# HE6-RORO2.net
KiCad netlist of a schematic drawn in EAGLE
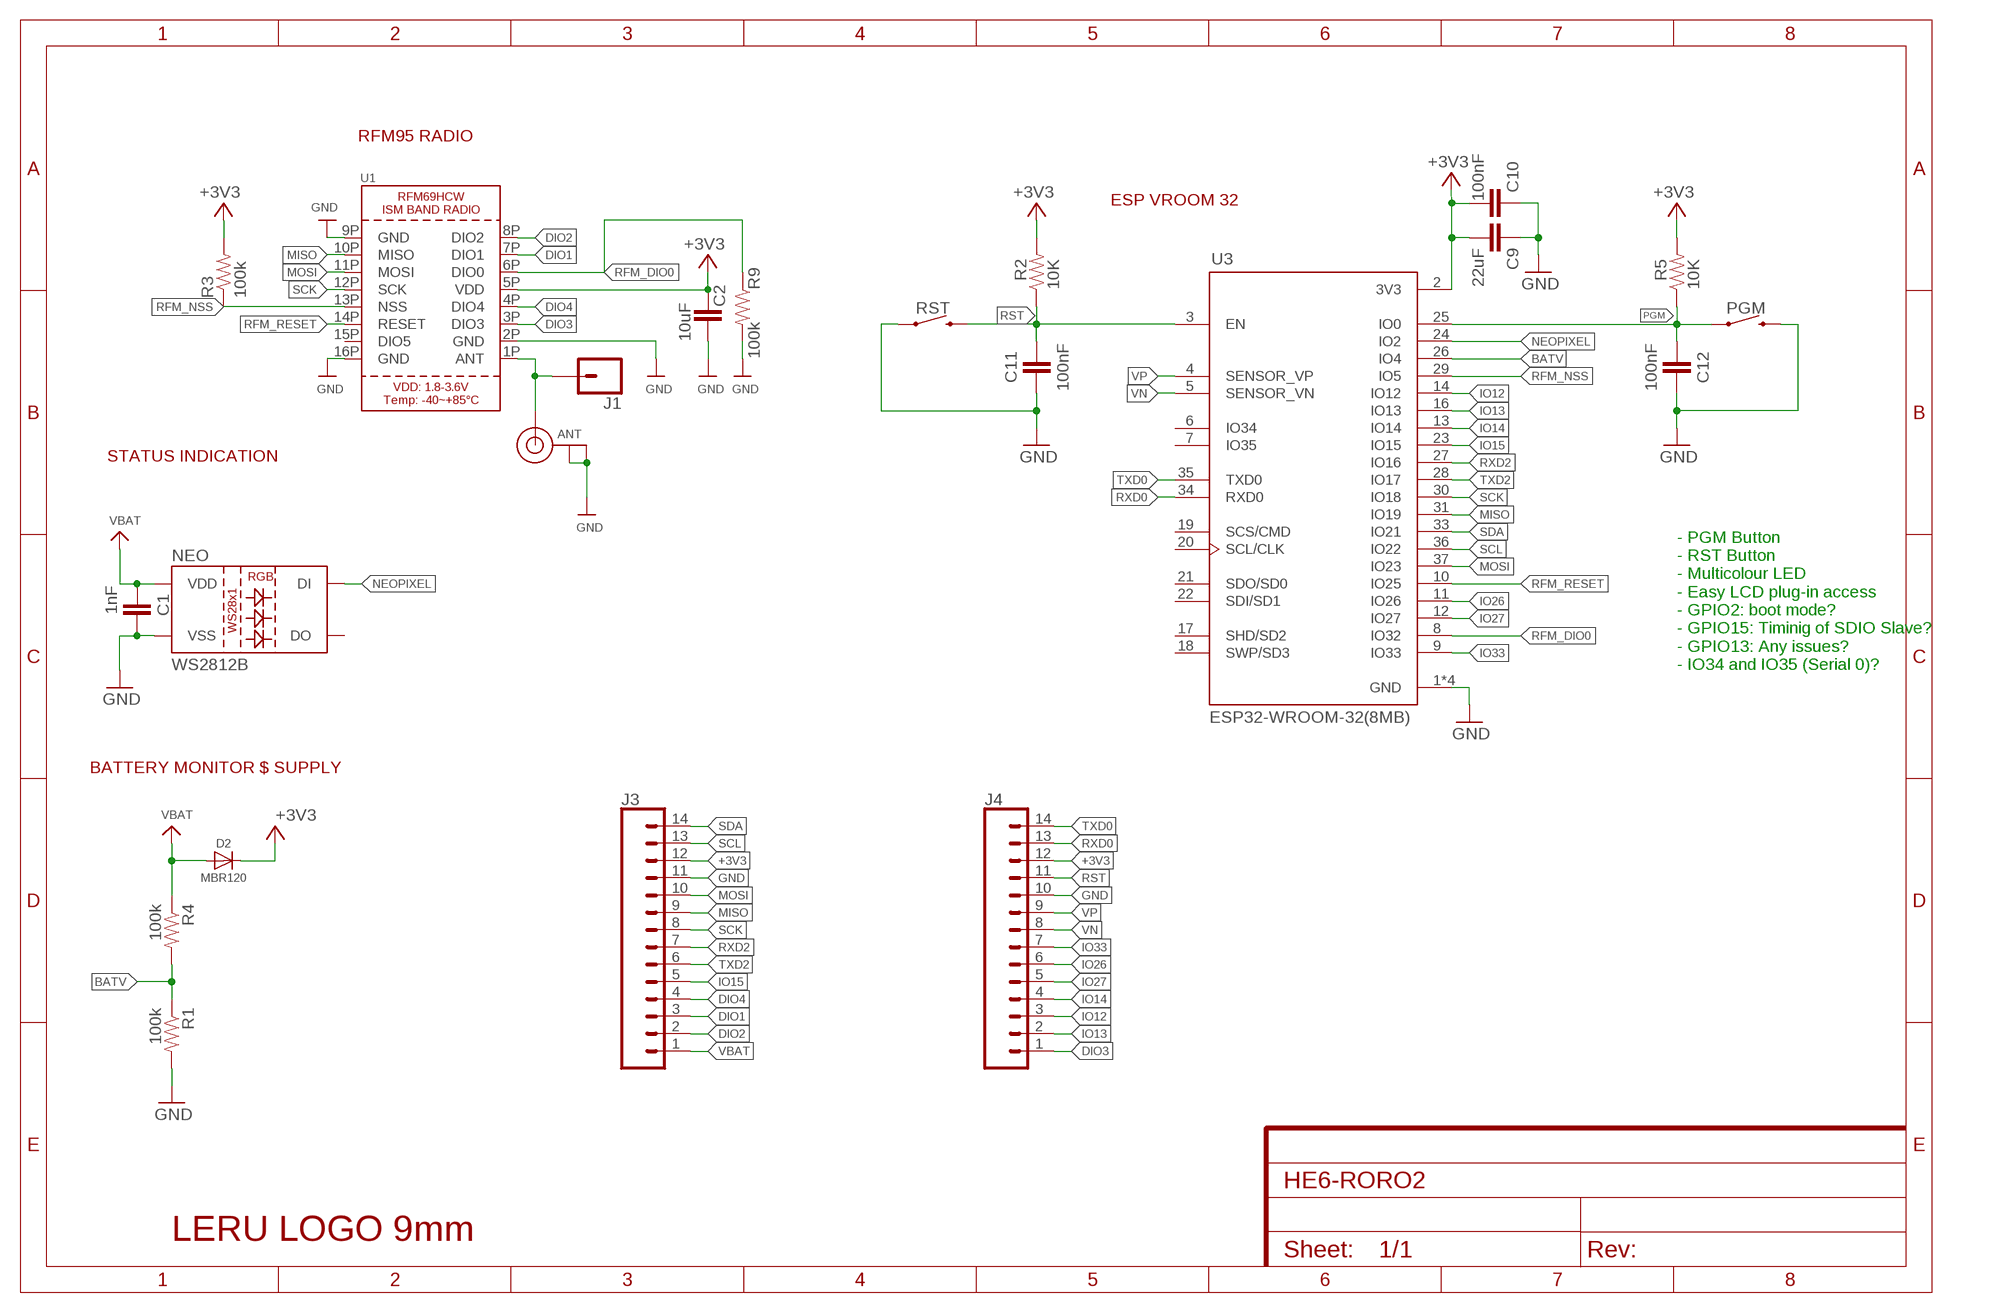
[diagram p0: schematic, sheet 1]

(export (version "E")
  (design (tool "Eeschema 10.0.6"))
  (components
    (comp (ref "ANT")
      (value "MICROBUILDER_ANTENNA_U.FL")
      (footprint "eagle-import:MICROBUILDER_U.FL")
      (libsource (lib "eagle-import") (part "MICROBUILDER_ANTENNA_U.FL"))
    )
    (comp (ref "C1")
      (value "1nF")
      (footprint "eagle-import:CAP")
      (libsource (lib "eagle-import") (part "CAP0805"))
    )
    (comp (ref "C2")
      (value "10uF")
      (footprint "eagle-import:CAP")
      (libsource (lib "eagle-import") (part "CAP0805"))
    )
    (comp (ref "C9")
      (value "22uF")
      (footprint "eagle-import:CAP")
      (libsource (lib "eagle-import") (part "CAP0805"))
    )
    (comp (ref "C10")
      (value "100nF")
      (footprint "eagle-import:CAP")
      (libsource (lib "eagle-import") (part "CAP0805"))
    )
    (comp (ref "C11")
      (value "100nF")
      (footprint "eagle-import:CAP")
      (libsource (lib "eagle-import") (part "CAP0805"))
    )
    (comp (ref "C12")
      (value "100nF")
      (footprint "eagle-import:CAP")
      (libsource (lib "eagle-import") (part "CAP0805"))
    )
    (comp (ref "D2")
      (value "MBR120")
      (footprint "eagle-import:DIODE")
      (libsource (lib "eagle-import") (part "DIODESOD123"))
    )
    (comp (ref "J1")
      (value "CONN_01PTH_NO_SILK_YES_STOP")
      (footprint "eagle-import:1X01_NO_SILK")
      (libsource (lib "eagle-import") (part "CONN_01PTH_NO_SILK_YES_STOP"))
    )
    (comp (ref "J3")
      (value "CONN_14NO_SILK")
      (footprint "eagle-import:1X14_NO_SILK")
      (libsource (lib "eagle-import") (part "CONN_14NO_SILK"))
    )
    (comp (ref "J4")
      (value "CONN_14NO_SILK")
      (footprint "eagle-import:1X14_NO_SILK")
      (libsource (lib "eagle-import") (part "CONN_14NO_SILK"))
    )
    (comp (ref "NEO")
      (value "WS2812B")
      (footprint "eagle-import:WS2812B")
      (libsource (lib "eagle-import") (part "WS2812B"))
    )
    (comp (ref "PGM")
      (value "MOMENTARY-SWITCH-SPST-SMD-RIGHT-ANGLE")
      (footprint "eagle-import:TACTILE_SWITCH_SMD_RIGHT_ANGLE")
      (libsource (lib "eagle-import") (part "MOMENTARY-SWITCH-SPST-SMD-RIGHT-ANGLE"))
    )
    (comp (ref "R1")
      (value "100k")
      (footprint "eagle-import:RES")
      (libsource (lib "eagle-import") (part "RES0805-RES"))
    )
    (comp (ref "R2")
      (value "10K")
      (footprint "eagle-import:RES")
      (libsource (lib "eagle-import") (part "RES0805-RES"))
    )
    (comp (ref "R3")
      (value "100k")
      (footprint "eagle-import:RES")
      (libsource (lib "eagle-import") (part "RES0805-RES"))
    )
    (comp (ref "R4")
      (value "100k")
      (footprint "eagle-import:RES")
      (libsource (lib "eagle-import") (part "RES0805-RES"))
    )
    (comp (ref "R5")
      (value "10K")
      (footprint "eagle-import:RES")
      (libsource (lib "eagle-import") (part "RES0805-RES"))
    )
    (comp (ref "R9")
      (value "100k")
      (footprint "eagle-import:RES")
      (libsource (lib "eagle-import") (part "RES0805-RES"))
    )
    (comp (ref "RST")
      (value "MOMENTARY-SWITCH-SPST-SMD-RIGHT-ANGLE")
      (footprint "eagle-import:TACTILE_SWITCH_SMD_RIGHT_ANGLE")
      (libsource (lib "eagle-import") (part "MOMENTARY-SWITCH-SPST-SMD-RIGHT-ANGLE"))
    )
    (comp (ref "U$9")
      (value "LERU_LOGO_9MM")
      (footprint "eagle-import:LERU_LOGO_9MM")
      (libsource (lib "eagle-import") (part "LERU_LOGO_9MM"))
    )
    (comp (ref "U1")
      (value "RFM69HCW_SMT")
      (footprint "eagle-import:RFMHCW_SMT")
      (libsource (lib "eagle-import") (part "RFM69HCW_SMT"))
    )
    (comp (ref "U3")
      (value "ESP32-WROOM-32(8MB)")
      (footprint "eagle-import:MODULE_ESP32-WROOM-32(8MB)")
      (fields (field (name "MF") "Espressif Systems") (field (name "MP") "ESP32-WROOM-32 _8MB_"))
      (libsource (lib "eagle-import") (part "ESP32-WROOM-32(8MB)"))
    )
  )
  (nets
    (net (code "1") (name "+3V3") (class "Default")
      (node (ref "C10") (pin "2") (pinfunction "2_2") (pintype "passive"))
      (node (ref "C2") (pin "1") (pinfunction "1_1") (pintype "passive"))
      (node (ref "C9") (pin "2") (pinfunction "2_2") (pintype "passive"))
      (node (ref "D2") (pin "1") (pinfunction "C_1") (pintype "passive"))
      (node (ref "J3") (pin "12") (pinfunction "12_12") (pintype "passive"))
      (node (ref "J4") (pin "12") (pinfunction "12_12") (pintype "passive"))
      (node (ref "R2") (pin "2") (pinfunction "2_2") (pintype "passive"))
      (node (ref "R3") (pin "2") (pinfunction "2_2") (pintype "passive"))
      (node (ref "R5") (pin "2") (pinfunction "2_2") (pintype "passive"))
      (node (ref "U1") (pin "5P") (pinfunction "VDD_5P") (pintype "power_in"))
      (node (ref "U3") (pin "2") (pinfunction "3V3_2") (pintype "power_in"))
    )
    (net (code "2") (name "BATV") (class "Default")
      (node (ref "R1") (pin "1") (pinfunction "1_1") (pintype "passive"))
      (node (ref "R4") (pin "2") (pinfunction "2_2") (pintype "passive"))
      (node (ref "U3") (pin "26") (pinfunction "IO4_26") (pintype "bidirectional"))
    )
    (net (code "3") (name "DIO1") (class "Default")
      (node (ref "J3") (pin "3") (pinfunction "3_3") (pintype "passive"))
      (node (ref "U1") (pin "7P") (pinfunction "DIO1_7P") (pintype "bidirectional"))
    )
    (net (code "4") (name "DIO2") (class "Default")
      (node (ref "J3") (pin "2") (pinfunction "2_2") (pintype "passive"))
      (node (ref "U1") (pin "8P") (pinfunction "DIO2_8P") (pintype "bidirectional"))
    )
    (net (code "5") (name "DIO3") (class "Default")
      (node (ref "J4") (pin "1") (pinfunction "1_1") (pintype "passive"))
      (node (ref "U1") (pin "3P") (pinfunction "DIO3_3P") (pintype "bidirectional"))
    )
    (net (code "6") (name "DIO4") (class "Default")
      (node (ref "J3") (pin "4") (pinfunction "4_4") (pintype "passive"))
      (node (ref "U1") (pin "4P") (pinfunction "DIO4_4P") (pintype "bidirectional"))
    )
    (net (code "7") (name "GND") (class "Default")
      (node (ref "ANT") (pin "1") (pinfunction "GND_1") (pintype "passive"))
      (node (ref "ANT") (pin "2") (pinfunction "GND_2") (pintype "passive"))
      (node (ref "C1") (pin "1") (pinfunction "1_1") (pintype "passive"))
      (node (ref "C10") (pin "1") (pinfunction "1_1") (pintype "passive"))
      (node (ref "C11") (pin "1") (pinfunction "1_1") (pintype "passive"))
      (node (ref "C12") (pin "1") (pinfunction "1_1") (pintype "passive"))
      (node (ref "C2") (pin "2") (pinfunction "2_2") (pintype "passive"))
      (node (ref "C9") (pin "1") (pinfunction "1_1") (pintype "passive"))
      (node (ref "J3") (pin "11") (pinfunction "11_11") (pintype "passive"))
      (node (ref "J4") (pin "10") (pinfunction "10_10") (pintype "passive"))
      (node (ref "NEO") (pin "3") (pinfunction "VSS_3") (pintype "bidirectional"))
      (node (ref "PGM") (pin "2") (pinfunction "2_2") (pintype "passive"))
      (node (ref "R1") (pin "2") (pinfunction "2_2") (pintype "passive"))
      (node (ref "R9") (pin "2") (pinfunction "2_2") (pintype "passive"))
      (node (ref "RST") (pin "1") (pinfunction "1_1") (pintype "passive"))
      (node (ref "U1") (pin "16P") (pinfunction "GND_16P") (pintype "power_in"))
      (node (ref "U1") (pin "2P") (pinfunction "GND_2P") (pintype "power_in"))
      (node (ref "U1") (pin "9P") (pinfunction "GND_9P") (pintype "power_in"))
      (node (ref "U3") (pin "1") (pinfunction "GND_1") (pintype "power_in"))
      (node (ref "U3") (pin "15") (pinfunction "GND_15") (pintype "power_in"))
      (node (ref "U3") (pin "38") (pinfunction "GND_38") (pintype "power_in"))
      (node (ref "U3") (pin "39") (pinfunction "GND_39") (pintype "power_in"))
    )
    (net (code "8") (name "IO12") (class "Default")
      (node (ref "J4") (pin "3") (pinfunction "3_3") (pintype "passive"))
      (node (ref "U3") (pin "14") (pinfunction "IO12_14") (pintype "bidirectional"))
    )
    (net (code "9") (name "IO13") (class "Default")
      (node (ref "J4") (pin "2") (pinfunction "2_2") (pintype "passive"))
      (node (ref "U3") (pin "16") (pinfunction "IO13_16") (pintype "bidirectional"))
    )
    (net (code "10") (name "IO14") (class "Default")
      (node (ref "J4") (pin "4") (pinfunction "4_4") (pintype "passive"))
      (node (ref "U3") (pin "13") (pinfunction "IO14_13") (pintype "bidirectional"))
    )
    (net (code "11") (name "IO15") (class "Default")
      (node (ref "J3") (pin "5") (pinfunction "5_5") (pintype "passive"))
      (node (ref "U3") (pin "23") (pinfunction "IO15_23") (pintype "bidirectional"))
    )
    (net (code "12") (name "IO26") (class "Default")
      (node (ref "J4") (pin "6") (pinfunction "6_6") (pintype "passive"))
      (node (ref "U3") (pin "11") (pinfunction "IO26_11") (pintype "bidirectional"))
    )
    (net (code "13") (name "IO27") (class "Default")
      (node (ref "J4") (pin "5") (pinfunction "5_5") (pintype "passive"))
      (node (ref "U3") (pin "12") (pinfunction "IO27_12") (pintype "bidirectional"))
    )
    (net (code "14") (name "IO33") (class "Default")
      (node (ref "J4") (pin "7") (pinfunction "7_7") (pintype "passive"))
      (node (ref "U3") (pin "9") (pinfunction "IO33_9") (pintype "bidirectional"))
    )
    (net (code "15") (name "MISO") (class "Default")
      (node (ref "J3") (pin "9") (pinfunction "9_9") (pintype "passive"))
      (node (ref "U1") (pin "10P") (pinfunction "MISO_10P") (pintype "output"))
      (node (ref "U3") (pin "31") (pinfunction "IO19_31") (pintype "bidirectional"))
    )
    (net (code "16") (name "MOSI") (class "Default")
      (node (ref "J3") (pin "10") (pinfunction "10_10") (pintype "passive"))
      (node (ref "U1") (pin "11P") (pinfunction "MOSI_11P") (pintype "input"))
      (node (ref "U3") (pin "37") (pinfunction "IO23_37") (pintype "bidirectional"))
    )
    (net (code "17") (name "NEOPIXEL") (class "Default")
      (node (ref "NEO") (pin "4") (pinfunction "DI_4") (pintype "bidirectional"))
      (node (ref "U3") (pin "24") (pinfunction "IO2_24") (pintype "bidirectional"))
    )
    (net (code "18") (name "Net-(ANT-SIGNAL)") (class "Default")
      (node (ref "ANT") (pin "3") (pinfunction "SIGNAL_3") (pintype "passive"))
      (node (ref "J1") (pin "1") (pinfunction "1_1") (pintype "passive"))
      (node (ref "U1") (pin "1P") (pinfunction "ANT_1P") (pintype "bidirectional"))
    )
    (net (code "19") (name "PGM") (class "Default")
      (node (ref "C12") (pin "2") (pinfunction "2_2") (pintype "passive"))
      (node (ref "PGM") (pin "1") (pinfunction "1_1") (pintype "passive"))
      (node (ref "R5") (pin "1") (pinfunction "1_1") (pintype "passive"))
      (node (ref "U3") (pin "25") (pinfunction "IO0_25") (pintype "bidirectional"))
    )
    (net (code "20") (name "RFM_DIO0") (class "Default")
      (node (ref "R9") (pin "1") (pinfunction "1_1") (pintype "passive"))
      (node (ref "U1") (pin "6P") (pinfunction "DIO0_6P") (pintype "bidirectional"))
      (node (ref "U3") (pin "8") (pinfunction "IO32_8") (pintype "bidirectional"))
    )
    (net (code "21") (name "RFM_NSS") (class "Default")
      (node (ref "R3") (pin "1") (pinfunction "1_1") (pintype "passive"))
      (node (ref "U1") (pin "13P") (pinfunction "NSS_13P") (pintype "input"))
      (node (ref "U3") (pin "29") (pinfunction "IO5_29") (pintype "bidirectional"))
    )
    (net (code "22") (name "RFM_RESET") (class "Default")
      (node (ref "U1") (pin "14P") (pinfunction "RESET_14P") (pintype "input"))
      (node (ref "U3") (pin "10") (pinfunction "IO25_10") (pintype "bidirectional"))
    )
    (net (code "23") (name "RST") (class "Default")
      (node (ref "C11") (pin "2") (pinfunction "2_2") (pintype "passive"))
      (node (ref "J4") (pin "11") (pinfunction "11_11") (pintype "passive"))
      (node (ref "R2") (pin "1") (pinfunction "1_1") (pintype "passive"))
      (node (ref "RST") (pin "2") (pinfunction "2_2") (pintype "passive"))
      (node (ref "U3") (pin "3") (pinfunction "EN_3") (pintype "input"))
    )
    (net (code "24") (name "RXD0") (class "Default")
      (node (ref "J4") (pin "13") (pinfunction "13_13") (pintype "passive"))
      (node (ref "U3") (pin "34") (pinfunction "RXD0_34") (pintype "bidirectional"))
    )
    (net (code "25") (name "RXD2") (class "Default")
      (node (ref "J3") (pin "7") (pinfunction "7_7") (pintype "passive"))
      (node (ref "U3") (pin "27") (pinfunction "IO16_27") (pintype "bidirectional"))
    )
    (net (code "26") (name "SCK") (class "Default")
      (node (ref "J3") (pin "8") (pinfunction "8_8") (pintype "passive"))
      (node (ref "U1") (pin "12P") (pinfunction "SCK_12P") (pintype "input"))
      (node (ref "U3") (pin "30") (pinfunction "IO18_30") (pintype "bidirectional"))
    )
    (net (code "27") (name "SCL") (class "Default")
      (node (ref "J3") (pin "13") (pinfunction "13_13") (pintype "passive"))
      (node (ref "U3") (pin "36") (pinfunction "IO22_36") (pintype "bidirectional"))
    )
    (net (code "28") (name "SDA") (class "Default")
      (node (ref "J3") (pin "14") (pinfunction "14_14") (pintype "passive"))
      (node (ref "U3") (pin "33") (pinfunction "IO21_33") (pintype "bidirectional"))
    )
    (net (code "29") (name "TXD0") (class "Default")
      (node (ref "J4") (pin "14") (pinfunction "14_14") (pintype "passive"))
      (node (ref "U3") (pin "35") (pinfunction "TXD0_35") (pintype "bidirectional"))
    )
    (net (code "30") (name "TXD2") (class "Default")
      (node (ref "J3") (pin "6") (pinfunction "6_6") (pintype "passive"))
      (node (ref "U3") (pin "28") (pinfunction "IO17_28") (pintype "bidirectional"))
    )
    (net (code "31") (name "VBAT") (class "Default")
      (node (ref "C1") (pin "2") (pinfunction "2_2") (pintype "passive"))
      (node (ref "D2") (pin "2") (pinfunction "A_2") (pintype "passive"))
      (node (ref "J3") (pin "1") (pinfunction "1_1") (pintype "passive"))
      (node (ref "NEO") (pin "1") (pinfunction "VDD_1") (pintype "bidirectional"))
      (node (ref "R4") (pin "1") (pinfunction "1_1") (pintype "passive"))
    )
    (net (code "32") (name "VN") (class "Default")
      (node (ref "J4") (pin "8") (pinfunction "8_8") (pintype "passive"))
      (node (ref "U3") (pin "5") (pinfunction "SENSOR_VN_5") (pintype "input"))
    )
    (net (code "33") (name "VP") (class "Default")
      (node (ref "J4") (pin "9") (pinfunction "9_9") (pintype "passive"))
      (node (ref "U3") (pin "4") (pinfunction "SENSOR_VP_4") (pintype "input"))
    )
    (net (code "34") (name "unconnected-(NEO-DO-Pad2)") (class "Default")
      (node (ref "NEO") (pin "2") (pinfunction "DO_2") (pintype "bidirectional"))
    )
    (net (code "35") (name "unconnected-(U1-DIO5-Pad15P)") (class "Default")
      (node (ref "U1") (pin "15P") (pinfunction "DIO5_15P") (pintype "bidirectional"))
    )
    (net (code "36") (name "unconnected-(U3-IO34-Pad6)") (class "Default")
      (node (ref "U3") (pin "6") (pinfunction "IO34_6") (pintype "input"))
    )
    (net (code "37") (name "unconnected-(U3-IO35-Pad7)") (class "Default")
      (node (ref "U3") (pin "7") (pinfunction "IO35_7") (pintype "input"))
    )
    (net (code "38") (name "unconnected-(U3-SCL{slash}CLK-Pad20)") (class "Default")
      (node (ref "U3") (pin "20") (pinfunction "SCL/CLK_20") (pintype "bidirectional"))
    )
    (net (code "39") (name "unconnected-(U3-SCS{slash}CMD-Pad19)") (class "Default")
      (node (ref "U3") (pin "19") (pinfunction "SCS/CMD_19") (pintype "bidirectional"))
    )
    (net (code "40") (name "unconnected-(U3-SDI{slash}SD1-Pad22)") (class "Default")
      (node (ref "U3") (pin "22") (pinfunction "SDI/SD1_22") (pintype "bidirectional"))
    )
    (net (code "41") (name "unconnected-(U3-SDO{slash}SD0-Pad21)") (class "Default")
      (node (ref "U3") (pin "21") (pinfunction "SDO/SD0_21") (pintype "bidirectional"))
    )
    (net (code "42") (name "unconnected-(U3-SHD{slash}SD2-Pad17)") (class "Default")
      (node (ref "U3") (pin "17") (pinfunction "SHD/SD2_17") (pintype "bidirectional"))
    )
    (net (code "43") (name "unconnected-(U3-SWP{slash}SD3-Pad18)") (class "Default")
      (node (ref "U3") (pin "18") (pinfunction "SWP/SD3_18") (pintype "bidirectional"))
    )
  )
)
